# POWER.net
KiCad netlist of a schematic drawn in Altium Designer
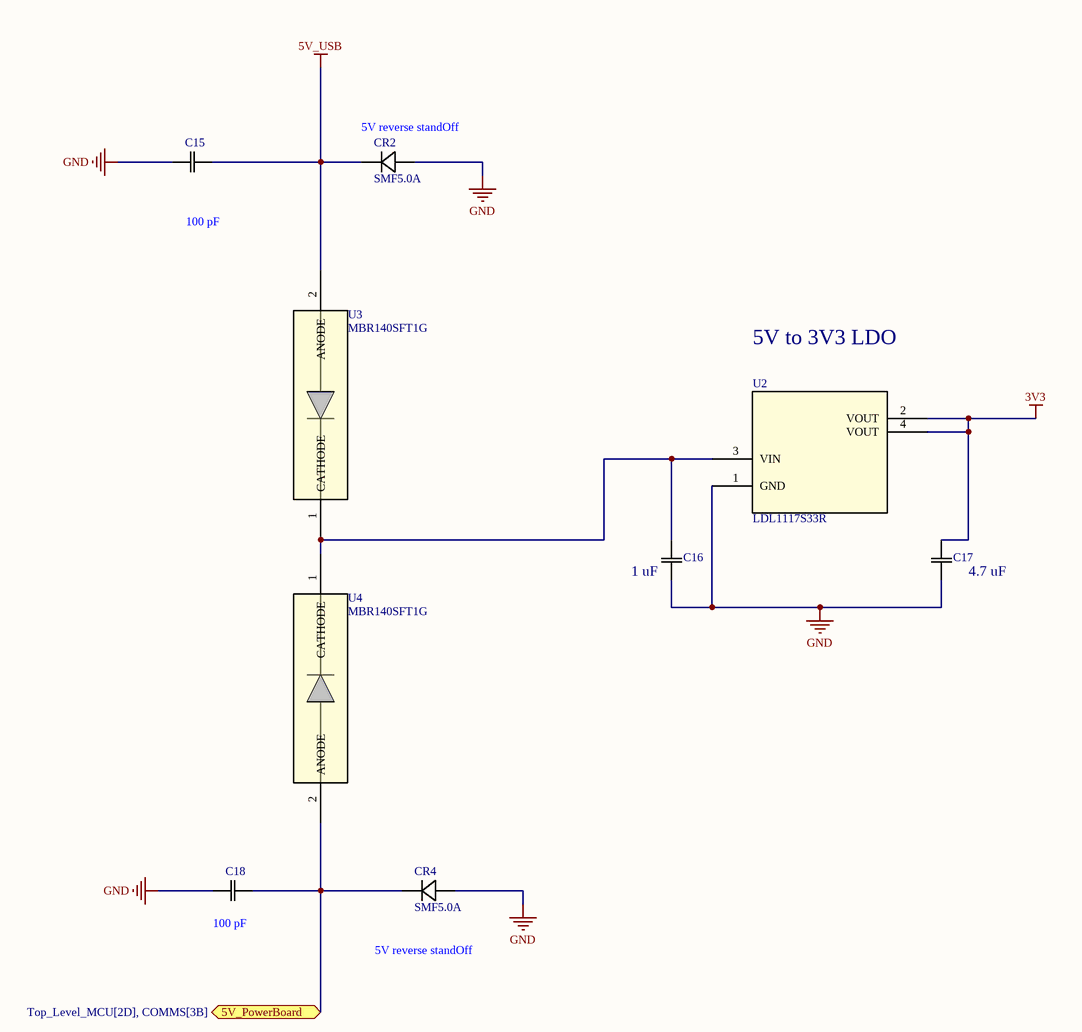
[diagram p0: POWER.SchDoc]

(export (version "E")
  (design (tool "Eeschema 10.0.6"))
  (components
    (comp (ref "C15")
      (value "CC0805KRX7R7BB104")
      (footprint "CC0805N_YAG")
      (description "Description")
      (fields (field (name "COPYRIGHT") "Copyright (C) 2025 Ultra Librarian. All rights reserved."))
      (libsource (lib "CC0805KRX7R7BB104") (part "CC0805KRX7R7BB104"))
    )
    (comp (ref "C16")
      (value "CC0805KRX7R7BB104")
      (footprint "CC0805N_YAG")
      (description "Description")
      (fields (field (name "COPYRIGHT") "Copyright (C) 2025 Ultra Librarian. All rights reserved."))
      (libsource (lib "CC0805KRX7R7BB104") (part "CC0805KRX7R7BB104"))
    )
    (comp (ref "C17")
      (value "CC0805KRX7R7BB104")
      (footprint "CC0805N_YAG")
      (description "Description")
      (fields (field (name "COPYRIGHT") "Copyright (C) 2025 Ultra Librarian. All rights reserved."))
      (libsource (lib "CC0805KRX7R7BB104") (part "CC0805KRX7R7BB104"))
    )
    (comp (ref "C18")
      (value "CC0805KRX7R7BB104")
      (footprint "CC0805N_YAG")
      (description "Description")
      (fields (field (name "COPYRIGHT") "Copyright (C) 2025 Ultra Librarian. All rights reserved."))
      (libsource (lib "CC0805KRX7R7BB104") (part "CC0805KRX7R7BB104"))
    )
    (comp (ref "CR2")
      (value "SMF5.0A")
      (footprint "SMFSeries_LTF")
      (description "Description")
      (fields (field (name "COPYRIGHT") "Copyright (C) 2025 Ultra Librarian. All rights reserved."))
      (libsource (lib "SMF5P0A") (part "SMF5.0A"))
    )
    (comp (ref "CR4")
      (value "SMF5.0A")
      (footprint "SMFSeries_LTF")
      (description "Description")
      (fields (field (name "COPYRIGHT") "Copyright (C) 2025 Ultra Librarian. All rights reserved."))
      (libsource (lib "SMF5P0A") (part "SMF5.0A"))
    )
    (comp (ref "U2")
      (value "LDL1117S33R")
      (footprint "SOT223_STM")
      (description "1.2 A High PSRR low dropout linear voltage regulator")
      (fields (field (name "COPYRIGHT") "Copyright (C) 2025 Ultra Librarian. All rights reserved."))
      (libsource (lib "LDL1117S33R") (part "LDL1117S33R"))
    )
    (comp (ref "U3")
      (value "MBR140SFT1G")
      (footprint "SOD_40SFT1G_ONS")
      (description "Description")
      (fields (field (name "COPYRIGHT") "Copyright (C) 2026 Ultra Librarian. All rights reserved."))
      (libsource (lib "MBR140SFT1G") (part "MBR140SFT1G"))
    )
    (comp (ref "U4")
      (value "MBR140SFT1G")
      (footprint "SOD_40SFT1G_ONS")
      (description "Description")
      (fields (field (name "COPYRIGHT") "Copyright (C) 2026 Ultra Librarian. All rights reserved."))
      (libsource (lib "") (part "MBR140SFT1G_1"))
    )
  )
  (nets
    (net (code "1") (name "/5V_PowerBoard") (class "Default")
      (node (ref "C18") (pin "2") (pinfunction "2_2") (pintype "passive"))
      (node (ref "CR4") (pin "1") (pinfunction "1_1") (pintype "passive"))
      (node (ref "U4") (pin "2") (pinfunction "ANODE_2") (pintype "passive"))
    )
    (net (code "2") (name "3V3") (class "Default")
      (node (ref "C17") (pin "2") (pinfunction "2_2") (pintype "passive"))
      (node (ref "U2") (pin "2") (pinfunction "VOUT_2") (pintype "power_in"))
      (node (ref "U2") (pin "4") (pinfunction "VOUT_4") (pintype "power_in"))
    )
    (net (code "3") (name "5V_USB") (class "Default")
      (node (ref "C15") (pin "2") (pinfunction "2_2") (pintype "passive"))
      (node (ref "CR2") (pin "1") (pinfunction "1_1") (pintype "passive"))
      (node (ref "U3") (pin "2") (pinfunction "ANODE_2") (pintype "passive"))
    )
    (net (code "4") (name "GND") (class "Default")
      (node (ref "C15") (pin "1") (pinfunction "1_1") (pintype "passive"))
      (node (ref "C16") (pin "1") (pinfunction "1_1") (pintype "passive"))
      (node (ref "C17") (pin "1") (pinfunction "1_1") (pintype "passive"))
      (node (ref "C18") (pin "1") (pinfunction "1_1") (pintype "passive"))
      (node (ref "CR2") (pin "2") (pinfunction "2_2") (pintype "passive"))
      (node (ref "CR4") (pin "2") (pinfunction "2_2") (pintype "passive"))
      (node (ref "U2") (pin "1") (pinfunction "GND_1") (pintype "power_in"))
    )
    (net (code "5") (name "Net-(U2-VIN)") (class "Default")
      (node (ref "C16") (pin "2") (pinfunction "2_2") (pintype "passive"))
      (node (ref "U2") (pin "3") (pinfunction "VIN_3") (pintype "power_in"))
      (node (ref "U3") (pin "1") (pinfunction "CATHODE_1") (pintype "passive"))
      (node (ref "U4") (pin "1") (pinfunction "CATHODE_1") (pintype "passive"))
    )
  )
)
